# N64_RGB_AV_Multiout_Breakout_PCB_v1.net
KiCad netlist of a schematic drawn in EAGLE
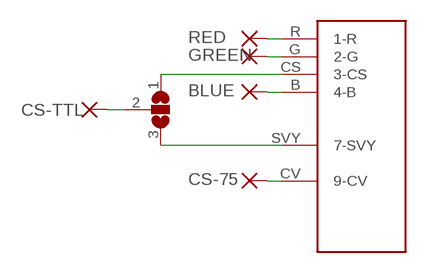
[diagram p0: schematic, sheet 1]

(export (version "E")
  (design (tool "Eeschema 10.0.6"))
  (components
    (comp (ref "BLUE")
      (value "BLUE")
      (footprint "eagle-import:RECTANGLE-1,27X2,54")
      (libsource (lib "eagle-import") (part "PADSRECTANGLE-1,27X2,54"))
    )
    (comp (ref "CS-75")
      (value "CS-75")
      (footprint "eagle-import:RECTANGLE-1,27X2,54")
      (libsource (lib "eagle-import") (part "PADSRECTANGLE-1,27X2,54"))
    )
    (comp (ref "CS-TTL")
      (value "CS-TTL")
      (footprint "eagle-import:RECTANGLE-1,27X2,54")
      (libsource (lib "eagle-import") (part "PADSRECTANGLE-1,27X2,54"))
    )
    (comp (ref "GREEN")
      (value "GREEN")
      (footprint "eagle-import:RECTANGLE-1,27X2,54")
      (libsource (lib "eagle-import") (part "PADSRECTANGLE-1,27X2,54"))
    )
    (comp (ref "N64-MULTIOUT")
      (value "N64-MULTIOUT")
      (footprint "eagle-import:N64-MULTIOUT")
      (libsource (lib "eagle-import") (part "N64-MULTIOUT"))
    )
    (comp (ref "RED")
      (value "RED")
      (footprint "eagle-import:RECTANGLE-1,27X2,54")
      (libsource (lib "eagle-import") (part "PADSRECTANGLE-1,27X2,54"))
    )
    (comp (ref "SJ1")
      (value "JUMPER-3JUMPER-3")
      (footprint "eagle-import:JUMPER-3")
      (libsource (lib "eagle-import") (part "JUMPER-3JUMPER-3"))
    )
  )
  (nets
    (net (code "1") (name "Net-(BLUE-P)") (class "Default")
      (node (ref "BLUE") (pin "1") (pinfunction "P_1") (pintype "passive"))
      (node (ref "N64-MULTIOUT") (pin "B") (pinfunction "4-B_B") (pintype "bidirectional"))
    )
    (net (code "2") (name "Net-(CS-75-P)") (class "Default")
      (node (ref "CS-75") (pin "1") (pinfunction "P_1") (pintype "passive"))
      (node (ref "N64-MULTIOUT") (pin "CV") (pinfunction "9-CV_CV") (pintype "bidirectional"))
    )
    (net (code "3") (name "Net-(CS-TTL-P)") (class "Default")
      (node (ref "CS-TTL") (pin "1") (pinfunction "P_1") (pintype "passive"))
      (node (ref "SJ1") (pin "2") (pinfunction "2_2") (pintype "passive"))
    )
    (net (code "4") (name "Net-(GREEN-P)") (class "Default")
      (node (ref "GREEN") (pin "1") (pinfunction "P_1") (pintype "passive"))
      (node (ref "N64-MULTIOUT") (pin "G") (pinfunction "2-G_G") (pintype "bidirectional"))
    )
    (net (code "5") (name "Net-(N64-MULTIOUT-1-R)") (class "Default")
      (node (ref "N64-MULTIOUT") (pin "R") (pinfunction "1-R_R") (pintype "bidirectional"))
      (node (ref "RED") (pin "1") (pinfunction "P_1") (pintype "passive"))
    )
    (net (code "6") (name "Net-(N64-MULTIOUT-3-CS)") (class "Default")
      (node (ref "N64-MULTIOUT") (pin "CS") (pinfunction "3-CS_CS") (pintype "bidirectional"))
      (node (ref "SJ1") (pin "1") (pinfunction "1_1") (pintype "passive"))
    )
    (net (code "7") (name "Net-(N64-MULTIOUT-7-SVY)") (class "Default")
      (node (ref "N64-MULTIOUT") (pin "SVY") (pinfunction "7-SVY_SVY") (pintype "bidirectional"))
      (node (ref "SJ1") (pin "3") (pinfunction "3_3") (pintype "passive"))
    )
  )
)
